# softSwitch.net
KiCad netlist of a schematic drawn in EAGLE
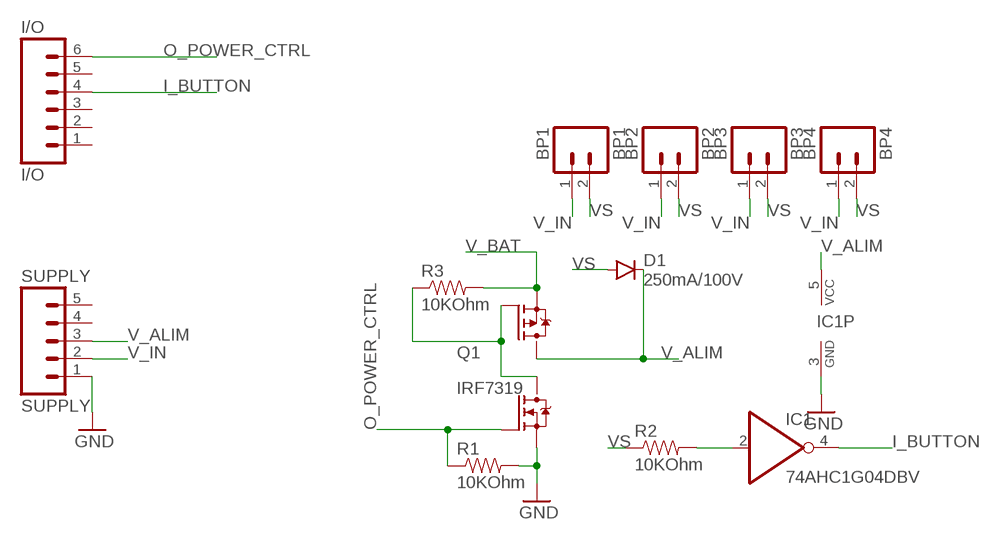
[diagram p0: schematic, sheet 1]

(export (version "E")
  (design (tool "Eeschema 10.0.6"))
  (components
    (comp (ref "BP1")
      (value "BP1")
      (footprint "eagle-import:1X02_NO_SILK")
      (libsource (lib "eagle-import") (part "M021X02_NO_SILK"))
    )
    (comp (ref "BP2")
      (value "BP2")
      (footprint "eagle-import:1X02_NO_SILK")
      (libsource (lib "eagle-import") (part "M021X02_NO_SILK"))
    )
    (comp (ref "BP3")
      (value "BP3")
      (footprint "eagle-import:1X02_NO_SILK")
      (libsource (lib "eagle-import") (part "M021X02_NO_SILK"))
    )
    (comp (ref "BP4")
      (value "BP4")
      (footprint "eagle-import:1X02_NO_SILK")
      (libsource (lib "eagle-import") (part "M021X02_NO_SILK"))
    )
    (comp (ref "D1")
      (value "250mA/100V")
      (footprint "eagle-import:SOD-323")
      (libsource (lib "eagle-import") (part "DIODEBAS16"))
    )
    (comp (ref "I/O")
      (value "I/O")
      (footprint "eagle-import:1X06_NO_SILK")
      (libsource (lib "eagle-import") (part "M06NO_SILK_FEMALE_PTH"))
    )
    (comp (ref "IC1")
      (value "74AHC1G04DBV")
      (footprint "eagle-import:SOT23-5")
      (libsource (lib "eagle-import") (part "741G04DBVAHC"))
    )
    (comp (ref "Q1")
      (value "IRF7319")
      (footprint "eagle-import:SO08-IRF")
      (libsource (lib "eagle-import") (part "IRF7319"))
    )
    (comp (ref "R1")
      (value "10KOhm")
      (footprint "eagle-import:0805")
      (libsource (lib "eagle-import") (part "RESISTOR0805-RES"))
    )
    (comp (ref "R2")
      (value "10KOhm")
      (footprint "eagle-import:0805")
      (libsource (lib "eagle-import") (part "RESISTOR0805-RES"))
    )
    (comp (ref "R3")
      (value "10KOhm")
      (footprint "eagle-import:0805")
      (libsource (lib "eagle-import") (part "RESISTOR0805-RES"))
    )
    (comp (ref "SUPPLY")
      (value "SUPPLY")
      (footprint "eagle-import:1X05_NO_SILK")
      (libsource (lib "eagle-import") (part "M05NO_SILK"))
    )
  )
  (nets
    (net (code "1") (name "/I_BUTTON") (class "Default")
      (node (ref "I/O") (pin "4") (pinfunction "4_4") (pintype "passive"))
      (node (ref "IC1") (pin "4") (pinfunction "O_4") (pintype "output"))
    )
    (net (code "2") (name "/O_POWER_CTRL") (class "Default")
      (node (ref "I/O") (pin "6") (pinfunction "6_6") (pintype "passive"))
      (node (ref "Q1") (pin "2") (pinfunction "N-G_2") (pintype "passive"))
      (node (ref "R1") (pin "1") (pinfunction "1_1") (pintype "passive"))
    )
    (net (code "3") (name "/VS") (class "Default")
      (node (ref "BP1") (pin "2") (pinfunction "2_2") (pintype "passive"))
      (node (ref "BP2") (pin "2") (pinfunction "2_2") (pintype "passive"))
      (node (ref "BP3") (pin "2") (pinfunction "2_2") (pintype "passive"))
      (node (ref "BP4") (pin "2") (pinfunction "2_2") (pintype "passive"))
      (node (ref "D1") (pin "A") (pinfunction "A_A") (pintype "passive"))
      (node (ref "R2") (pin "1") (pinfunction "1_1") (pintype "passive"))
    )
    (net (code "4") (name "/V_ALIM") (class "Default")
      (node (ref "D1") (pin "C") (pinfunction "C_C") (pintype "passive"))
      (node (ref "IC1") (pin "5") (pinfunction "VCC_5") (pintype "power_in"))
      (node (ref "Q1") (pin "5") (pinfunction "P-D_5") (pintype "passive"))
      (node (ref "Q1") (pin "6") (pinfunction "P-D_6") (pintype "passive"))
      (node (ref "SUPPLY") (pin "3") (pinfunction "3_3") (pintype "passive"))
    )
    (net (code "5") (name "/V_BAT") (class "Default")
      (node (ref "Q1") (pin "3") (pinfunction "P-S_3") (pintype "passive"))
      (node (ref "R3") (pin "2") (pinfunction "2_2") (pintype "passive"))
    )
    (net (code "6") (name "/V_IN") (class "Default")
      (node (ref "BP1") (pin "1") (pinfunction "1_1") (pintype "passive"))
      (node (ref "BP2") (pin "1") (pinfunction "1_1") (pintype "passive"))
      (node (ref "BP3") (pin "1") (pinfunction "1_1") (pintype "passive"))
      (node (ref "BP4") (pin "1") (pinfunction "1_1") (pintype "passive"))
      (node (ref "SUPPLY") (pin "2") (pinfunction "2_2") (pintype "passive"))
    )
    (net (code "7") (name "GND") (class "Default")
      (node (ref "IC1") (pin "3") (pinfunction "GND_3") (pintype "power_in"))
      (node (ref "Q1") (pin "1") (pinfunction "N-S_1") (pintype "passive"))
      (node (ref "R1") (pin "2") (pinfunction "2_2") (pintype "passive"))
      (node (ref "SUPPLY") (pin "1") (pinfunction "1_1") (pintype "passive"))
    )
    (net (code "8") (name "Net-(IC1A-I)") (class "Default")
      (node (ref "IC1") (pin "2") (pinfunction "I_2") (pintype "input"))
      (node (ref "R2") (pin "2") (pinfunction "2_2") (pintype "passive"))
    )
    (net (code "9") (name "Net-(Q1-P-G)") (class "Default")
      (node (ref "Q1") (pin "4") (pinfunction "P-G_4") (pintype "passive"))
      (node (ref "Q1") (pin "7") (pinfunction "N-D_7") (pintype "passive"))
      (node (ref "Q1") (pin "8") (pinfunction "N-D_8") (pintype "passive"))
      (node (ref "R3") (pin "1") (pinfunction "1_1") (pintype "passive"))
    )
    (net (code "10") (name "unconnected-(I/O-Pad1)") (class "Default")
      (node (ref "I/O") (pin "1") (pinfunction "1_1") (pintype "passive"))
    )
    (net (code "11") (name "unconnected-(I/O-Pad2)") (class "Default")
      (node (ref "I/O") (pin "2") (pinfunction "2_2") (pintype "passive"))
    )
    (net (code "12") (name "unconnected-(I/O-Pad3)") (class "Default")
      (node (ref "I/O") (pin "3") (pinfunction "3_3") (pintype "passive"))
    )
    (net (code "13") (name "unconnected-(I/O-Pad5)") (class "Default")
      (node (ref "I/O") (pin "5") (pinfunction "5_5") (pintype "passive"))
    )
    (net (code "14") (name "unconnected-(SUPPLY-Pad4)") (class "Default")
      (node (ref "SUPPLY") (pin "4") (pinfunction "4_4") (pintype "passive"))
    )
    (net (code "15") (name "unconnected-(SUPPLY-Pad5)") (class "Default")
      (node (ref "SUPPLY") (pin "5") (pinfunction "5_5") (pintype "passive"))
    )
  )
)
